# VibrationDrive.net
KiCad netlist of a schematic drawn in EAGLE
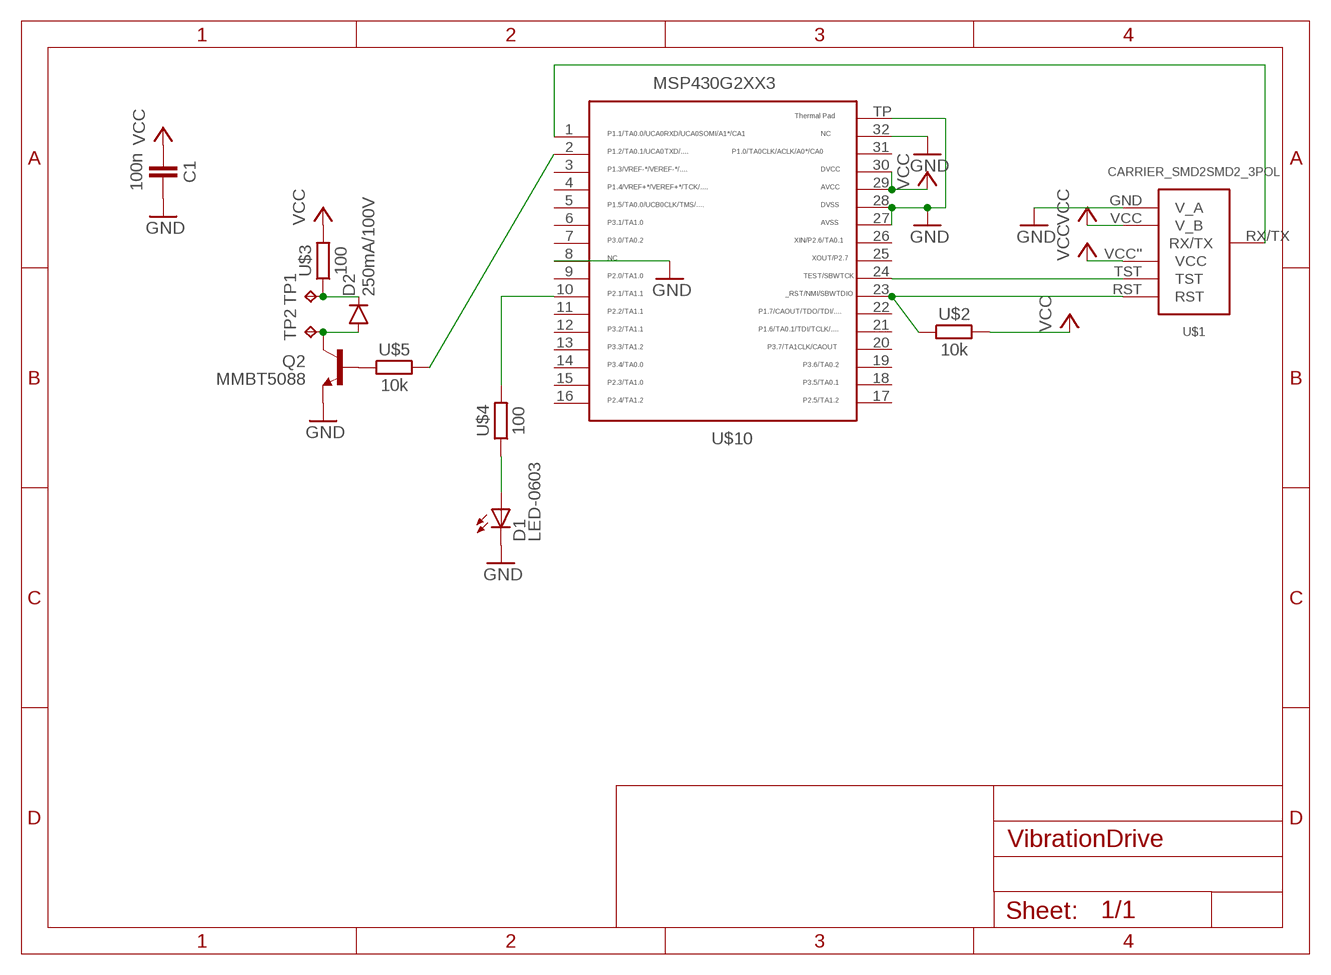
[diagram p0: schematic, sheet 1]

(export (version "E")
  (design (tool "Eeschema 10.0.6"))
  (components
    (comp (ref "C1")
      (value "100n")
      (footprint "eagle-import:603")
      (libsource (lib "eagle-import") (part "CAPACITOR"))
    )
    (comp (ref "D1")
      (value "LED-0603")
      (footprint "eagle-import:LED_0603")
      (libsource (lib "eagle-import") (part "LED-0603"))
    )
    (comp (ref "D2")
      (value "250mA/100V")
      (footprint "eagle-import:SOD-323")
      (libsource (lib "eagle-import") (part "DIODEBAS16"))
    )
    (comp (ref "Q2")
      (value "MMBT5088")
      (footprint "eagle-import:SOT23-3")
      (libsource (lib "eagle-import") (part "TRANSISTOR_NPNMMBT5088"))
    )
    (comp (ref "TP1")
      (value "TPTP20SQ")
      (footprint "eagle-import:TP20SQ")
      (libsource (lib "eagle-import") (part "TPTP20SQ"))
    )
    (comp (ref "TP2")
      (value "TPTP20SQ")
      (footprint "eagle-import:TP20SQ")
      (libsource (lib "eagle-import") (part "TPTP20SQ"))
    )
    (comp (ref "U$1")
      (value "CARRIER_SMD2SMD2_3POL")
      (footprint "eagle-import:CARRIER_SMD2_3POL")
      (libsource (lib "eagle-import") (part "CARRIER_SMD2SMD2_3POL"))
    )
    (comp (ref "U$2")
      (value "10k")
      (footprint "eagle-import:603")
      (libsource (lib "eagle-import") (part "RESISTOR0603"))
    )
    (comp (ref "U$3")
      (value "100")
      (footprint "eagle-import:603")
      (libsource (lib "eagle-import") (part "RESISTOR0603"))
    )
    (comp (ref "U$4")
      (value "100")
      (footprint "eagle-import:603")
      (libsource (lib "eagle-import") (part "RESISTOR0603"))
    )
    (comp (ref "U$5")
      (value "10k")
      (footprint "eagle-import:603")
      (libsource (lib "eagle-import") (part "RESISTOR0603"))
    )
    (comp (ref "U$10")
      (value "MSP430G2553")
      (footprint "eagle-import:QFN32")
      (libsource (lib "eagle-import") (part "MSP430G2553"))
    )
  )
  (nets
    (net (code "1") (name "GND") (class "Default")
      (node (ref "C1") (pin "2") (pinfunction "2_2") (pintype "passive"))
      (node (ref "D1") (pin "C") (pinfunction "C_C") (pintype "passive"))
      (node (ref "Q2") (pin "2") (pinfunction "E_2") (pintype "passive"))
      (node (ref "U$1") (pin "GND") (pinfunction "V_A_GND") (pintype "bidirectional"))
      (node (ref "U$10") (pin "27") (pinfunction "27_27") (pintype "bidirectional"))
      (node (ref "U$10") (pin "28") (pinfunction "28_28") (pintype "bidirectional"))
      (node (ref "U$10") (pin "32") (pinfunction "32_32") (pintype "bidirectional"))
      (node (ref "U$10") (pin "8") (pinfunction "8_8") (pintype "bidirectional"))
      (node (ref "U$10") (pin "TP") (pinfunction "TP_TP") (pintype "bidirectional"))
    )
    (net (code "2") (name "Net-(D1-PadA)") (class "Default")
      (node (ref "D1") (pin "A") (pinfunction "A_A") (pintype "passive"))
      (node (ref "U$4") (pin "1") (pinfunction "1_1") (pintype "passive"))
    )
    (net (code "3") (name "Net-(D2-PadC)") (class "Default")
      (node (ref "D2") (pin "C") (pinfunction "C_C") (pintype "passive"))
      (node (ref "TP1") (pin "TP") (pinfunction "TP_TP") (pintype "input"))
      (node (ref "U$3") (pin "1") (pinfunction "1_1") (pintype "passive"))
    )
    (net (code "4") (name "Net-(Q2-B)") (class "Default")
      (node (ref "Q2") (pin "1") (pinfunction "B_1") (pintype "passive"))
      (node (ref "U$5") (pin "1") (pinfunction "1_1") (pintype "passive"))
    )
    (net (code "5") (name "Net-(Q2-C)") (class "Default")
      (node (ref "D2") (pin "A") (pinfunction "A_A") (pintype "passive"))
      (node (ref "Q2") (pin "3") (pinfunction "C_3") (pintype "passive"))
      (node (ref "TP2") (pin "TP") (pinfunction "TP_TP") (pintype "input"))
    )
    (net (code "6") (name "Net-(U$1-PadRST)") (class "Default")
      (node (ref "U$1") (pin "RST") (pinfunction "RST_RST") (pintype "bidirectional"))
      (node (ref "U$10") (pin "23") (pinfunction "23_23") (pintype "bidirectional"))
      (node (ref "U$2") (pin "1") (pinfunction "1_1") (pintype "passive"))
    )
    (net (code "7") (name "Net-(U$1-PadRX{slash}TX)") (class "Default")
      (node (ref "U$1") (pin "RX/TX") (pinfunction "RX/TX_RX/TX") (pintype "bidirectional"))
      (node (ref "U$10") (pin "1") (pinfunction "1_1") (pintype "bidirectional"))
    )
    (net (code "8") (name "Net-(U$1-PadTST)") (class "Default")
      (node (ref "U$1") (pin "TST") (pinfunction "TST_TST") (pintype "bidirectional"))
      (node (ref "U$10") (pin "24") (pinfunction "24_24") (pintype "bidirectional"))
    )
    (net (code "9") (name "Net-(U$10-Pad2)") (class "Default")
      (node (ref "U$10") (pin "2") (pinfunction "2_2") (pintype "bidirectional"))
      (node (ref "U$5") (pin "2") (pinfunction "2_2") (pintype "passive"))
    )
    (net (code "10") (name "Net-(U$10-Pad10)") (class "Default")
      (node (ref "U$10") (pin "10") (pinfunction "10_10") (pintype "bidirectional"))
      (node (ref "U$4") (pin "2") (pinfunction "2_2") (pintype "passive"))
    )
    (net (code "11") (name "VCC") (class "Default")
      (node (ref "C1") (pin "1") (pinfunction "1_1") (pintype "passive"))
      (node (ref "U$1") (pin "VCC") (pinfunction "V_B_VCC") (pintype "bidirectional"))
      (node (ref "U$1") (pin "VCC''") (pinfunction "VCC_VCC''") (pintype "bidirectional"))
      (node (ref "U$10") (pin "29") (pinfunction "29_29") (pintype "bidirectional"))
      (node (ref "U$10") (pin "30") (pinfunction "30_30") (pintype "bidirectional"))
      (node (ref "U$2") (pin "2") (pinfunction "2_2") (pintype "passive"))
      (node (ref "U$3") (pin "2") (pinfunction "2_2") (pintype "passive"))
    )
    (net (code "12") (name "unconnected-(U$10-Pad3)") (class "Default")
      (node (ref "U$10") (pin "3") (pinfunction "3_3") (pintype "bidirectional"))
    )
    (net (code "13") (name "unconnected-(U$10-Pad4)") (class "Default")
      (node (ref "U$10") (pin "4") (pinfunction "4_4") (pintype "bidirectional"))
    )
    (net (code "14") (name "unconnected-(U$10-Pad5)") (class "Default")
      (node (ref "U$10") (pin "5") (pinfunction "5_5") (pintype "bidirectional"))
    )
    (net (code "15") (name "unconnected-(U$10-Pad6)") (class "Default")
      (node (ref "U$10") (pin "6") (pinfunction "6_6") (pintype "bidirectional"))
    )
    (net (code "16") (name "unconnected-(U$10-Pad7)") (class "Default")
      (node (ref "U$10") (pin "7") (pinfunction "7_7") (pintype "bidirectional"))
    )
    (net (code "17") (name "unconnected-(U$10-Pad9)") (class "Default")
      (node (ref "U$10") (pin "9") (pinfunction "9_9") (pintype "bidirectional"))
    )
    (net (code "18") (name "unconnected-(U$10-Pad11)") (class "Default")
      (node (ref "U$10") (pin "11") (pinfunction "11_11") (pintype "bidirectional"))
    )
    (net (code "19") (name "unconnected-(U$10-Pad12)") (class "Default")
      (node (ref "U$10") (pin "12") (pinfunction "12_12") (pintype "bidirectional"))
    )
    (net (code "20") (name "unconnected-(U$10-Pad13)") (class "Default")
      (node (ref "U$10") (pin "13") (pinfunction "13_13") (pintype "bidirectional"))
    )
    (net (code "21") (name "unconnected-(U$10-Pad14)") (class "Default")
      (node (ref "U$10") (pin "14") (pinfunction "14_14") (pintype "bidirectional"))
    )
    (net (code "22") (name "unconnected-(U$10-Pad15)") (class "Default")
      (node (ref "U$10") (pin "15") (pinfunction "15_15") (pintype "bidirectional"))
    )
    (net (code "23") (name "unconnected-(U$10-Pad16)") (class "Default")
      (node (ref "U$10") (pin "16") (pinfunction "16_16") (pintype "bidirectional"))
    )
    (net (code "24") (name "unconnected-(U$10-Pad17)") (class "Default")
      (node (ref "U$10") (pin "17") (pinfunction "17_17") (pintype "bidirectional"))
    )
    (net (code "25") (name "unconnected-(U$10-Pad18)") (class "Default")
      (node (ref "U$10") (pin "18") (pinfunction "18_18") (pintype "bidirectional"))
    )
    (net (code "26") (name "unconnected-(U$10-Pad19)") (class "Default")
      (node (ref "U$10") (pin "19") (pinfunction "19_19") (pintype "bidirectional"))
    )
    (net (code "27") (name "unconnected-(U$10-Pad20)") (class "Default")
      (node (ref "U$10") (pin "20") (pinfunction "20_20") (pintype "bidirectional"))
    )
    (net (code "28") (name "unconnected-(U$10-Pad21)") (class "Default")
      (node (ref "U$10") (pin "21") (pinfunction "21_21") (pintype "bidirectional"))
    )
    (net (code "29") (name "unconnected-(U$10-Pad22)") (class "Default")
      (node (ref "U$10") (pin "22") (pinfunction "22_22") (pintype "bidirectional"))
    )
    (net (code "30") (name "unconnected-(U$10-Pad25)") (class "Default")
      (node (ref "U$10") (pin "25") (pinfunction "25_25") (pintype "bidirectional"))
    )
    (net (code "31") (name "unconnected-(U$10-Pad26)") (class "Default")
      (node (ref "U$10") (pin "26") (pinfunction "26_26") (pintype "bidirectional"))
    )
    (net (code "32") (name "unconnected-(U$10-Pad31)") (class "Default")
      (node (ref "U$10") (pin "31") (pinfunction "31_31") (pintype "bidirectional"))
    )
  )
)
